# 1V2-BUCK.net
KiCad netlist of a schematic drawn in Altium Designer
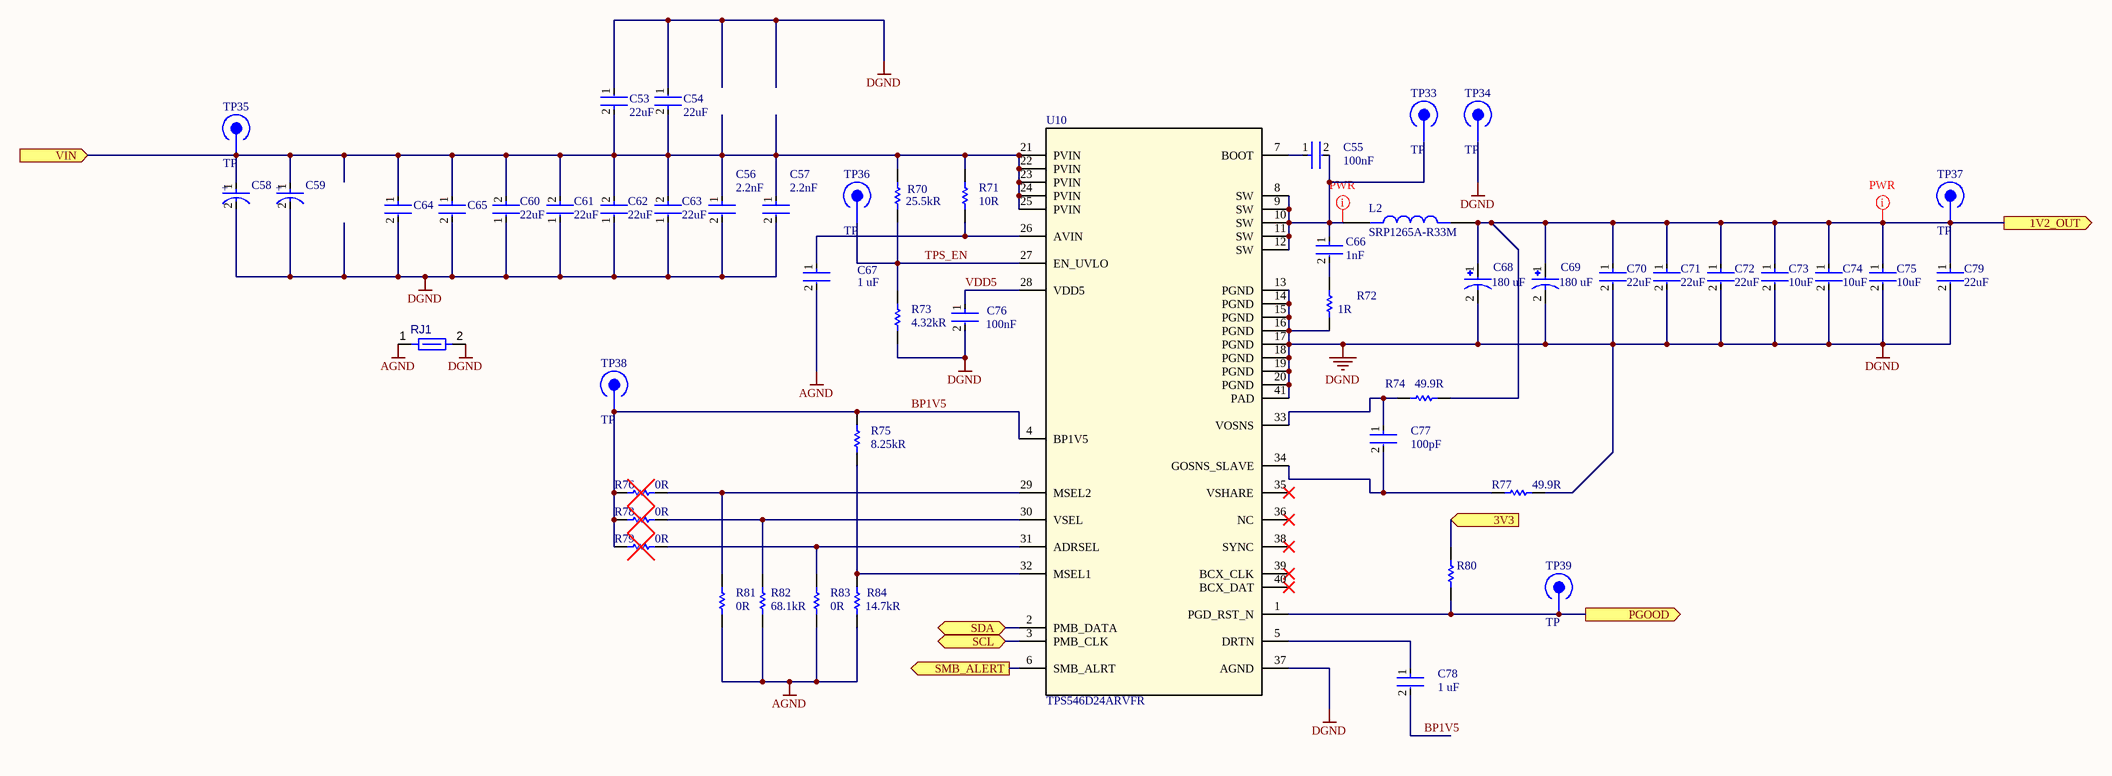
[diagram p0: 1V2-BUCK.SchDoc]

(export (version "E")
  (design (tool "Eeschema 10.0.6"))
  (components
    (comp (ref "C53")
      (value "GRM31CC81E226ME11L")
      (footprint "FP-GRM31C-0_3-e0_3_0_8-MFG")
      (description "Chip Multilayer Ceramic Capacitors for General Purpose, 1206, 22uF, X6S, 22%, 20%, 25V")
      (fields (field (name "CAPACITANCE") "22uF") (field (name "TOLERANCE") "20%"))
      (libsource (lib "Altium Content Vault") (part "f23184f103b6ebe33a8c269c53dcba6"))
    )
    (comp (ref "C54")
      (value "GRM31CC81E226ME11L")
      (footprint "FP-GRM31C-0_3-e0_3_0_8-MFG")
      (description "Chip Multilayer Ceramic Capacitors for General Purpose, 1206, 22uF, X6S, 22%, 20%, 25V")
      (fields (field (name "CAPACITANCE") "22uF") (field (name "TOLERANCE") "20%"))
      (libsource (lib "Altium Content Vault") (part "f23184f103b6ebe33a8c269c53dcba6"))
    )
    (comp (ref "C55")
      (value "100nF")
      (footprint "FP-CC0402-IPC_B")
      (fields (field (name "Comment") "CC0402KRX7R9BB104"))
      (libsource (lib "Digital Shovel") (part "11868f565c42a9108669ba33697ecf6"))
    )
    (comp (ref "C56")
      (value "2.2nF")
      (footprint "FP-CC0402-MFG")
      (fields (field (name "Comment") "CC0402KRX7R8BB222"))
      (libsource (lib "Digital Shovel") (part "11868f565c42a9108669ba33697ecf6"))
    )
    (comp (ref "C57")
      (value "2.2nF")
      (footprint "FP-CC0402-MFG")
      (fields (field (name "Comment") "CC0402KRX7R8BB222"))
      (libsource (lib "Digital Shovel") (part "11868f565c42a9108669ba33697ecf6"))
    )
    (comp (ref "C58")
      (value "593D107X9020E2TE3")
      (footprint "593D107X9020E2TE3-Footprint-1")
      (description "No Description Available")
      (libsource (lib "Digital Shovel") (part "593D107X9020E2TE3"))
    )
    (comp (ref "C59")
      (value "593D107X9020E2TE3")
      (footprint "593D107X9020E2TE3-Footprint-1")
      (description "No Description Available")
      (libsource (lib "Digital Shovel") (part "593D107X9020E2TE3"))
    )
    (comp (ref "C60")
      (value "GRM31CC81E226ME11L")
      (footprint "FP-GRM31C-0_3-e0_3_0_8-MFG")
      (description "Chip Multilayer Ceramic Capacitors for General Purpose, 1206, 22uF, X6S, 22%, 20%, 25V")
      (fields (field (name "CAPACITANCE") "22uF") (field (name "TOLERANCE") "20%"))
      (libsource (lib "Altium Content Vault") (part "f23184f103b6ebe33a8c269c53dcba6"))
    )
    (comp (ref "C61")
      (value "GRM31CC81E226ME11L")
      (footprint "FP-GRM31C-0_3-e0_3_0_8-MFG")
      (description "Chip Multilayer Ceramic Capacitors for General Purpose, 1206, 22uF, X6S, 22%, 20%, 25V")
      (fields (field (name "CAPACITANCE") "22uF") (field (name "TOLERANCE") "20%"))
      (libsource (lib "Altium Content Vault") (part "f23184f103b6ebe33a8c269c53dcba6"))
    )
    (comp (ref "C62")
      (value "GRM31CC81E226ME11L")
      (footprint "FP-GRM31C-0_3-e0_3_0_8-MFG")
      (description "Chip Multilayer Ceramic Capacitors for General Purpose, 1206, 22uF, X6S, 22%, 20%, 25V")
      (fields (field (name "CAPACITANCE") "22uF") (field (name "TOLERANCE") "20%"))
      (libsource (lib "Altium Content Vault") (part "f23184f103b6ebe33a8c269c53dcba6"))
    )
    (comp (ref "C63")
      (value "GRM31CC81E226ME11L")
      (footprint "FP-GRM31C-0_3-e0_3_0_8-MFG")
      (description "Chip Multilayer Ceramic Capacitors for General Purpose, 1206, 22uF, X6S, 22%, 20%, 25V")
      (fields (field (name "CAPACITANCE") "22uF") (field (name "TOLERANCE") "20%"))
      (libsource (lib "Altium Content Vault") (part "f23184f103b6ebe33a8c269c53dcba6"))
    )
    (comp (ref "C64")
      (value "C3216X5R1E476M160AC")
      (footprint "FP-C3216-160-0_2-MFG")
      (description "Multilayer Ceramic Capacitors 47uF ±20% 25V X5R SMD 1206")
      (fields (field (name "VOLTAGE") "25V") (field (name "TOLERANCE") "20%"))
      (libsource (lib "Altium Content Vault") (part "11868f565c42a9108669ba33697ecf6"))
    )
    (comp (ref "C65")
      (value "C3216X5R1E476M160AC")
      (footprint "FP-C3216-160-0_2-MFG")
      (description "Multilayer Ceramic Capacitors 47uF ±20% 25V X5R SMD 1206")
      (fields (field (name "VOLTAGE") "25V") (field (name "TOLERANCE") "20%"))
      (libsource (lib "Altium Content Vault") (part "11868f565c42a9108669ba33697ecf6"))
    )
    (comp (ref "C66")
      (value "1nF")
      (footprint "FP-CC0805-0_85-MFG")
      (fields (field (name "Comment") "CC0805KRX7R9BB102"))
      (libsource (lib "Digital Shovel") (part "11868f565c42a9108669ba33697ecf6"))
    )
    (comp (ref "C67")
      (value "1 uF")
      (footprint "FP-CC0402-MFG")
      (description "CAP CER 1UF 10V X5R 0402")
      (fields
        (field (name "OCTOPART") "https://octopart.com/cc0402krx5r6bb105-yageo-42244620")
        (field (name "MANUFACTURER PART NUMBER") "CC0402KRX5R6BB105")
      )
      (libsource (lib "Altium Content Vault") (part "11868f565c42a9108669ba33697ecf6"))
    )
    (comp (ref "C68")
      (value "180 uF")
      (footprint "EEF-SX0J181ER-Footprint-1")
      (description "Cap Aluminum Polymer 180uF 6.3VDC 20%( 7.3 X 4.3 X 1.9mm) SMD 0.009 Ohm 6300mA 2000h 105C T/R")
      (fields (field (name "MANUFACTURER") "Panasonic") (field (name "Comment") "EEF-SX0J181ER"))
      (libsource (lib "Digital Shovel") (part "EEF-SX0J181ER-Symbol-1"))
    )
    (comp (ref "C69")
      (value "180 uF")
      (footprint "EEF-SX0J181ER-Footprint-1")
      (description "Cap Aluminum Polymer 180uF 6.3VDC 20%( 7.3 X 4.3 X 1.9mm) SMD 0.009 Ohm 6300mA 2000h 105C T/R")
      (fields (field (name "MANUFACTURER") "Panasonic") (field (name "Comment") "EEF-SX0J181ER"))
      (libsource (lib "Digital Shovel") (part "EEF-SX0J181ER-Symbol-1"))
    )
    (comp (ref "C70")
      (value "22uF")
      (footprint "FP-GRM21B-0_2-e0_2_0_7-MFG")
      (fields (field (name "Comment") "GRM21BZ70J226ME44L"))
      (libsource (lib "Digital Shovel") (part "b4654b650e69147ec39a6b967a45e02"))
    )
    (comp (ref "C71")
      (value "22uF")
      (footprint "FP-GRM21B-0_2-e0_2_0_7-MFG")
      (fields (field (name "Comment") "GRM21BZ70J226ME44L"))
      (libsource (lib "Digital Shovel") (part "b4654b650e69147ec39a6b967a45e02"))
    )
    (comp (ref "C72")
      (value "22uF")
      (footprint "FP-GRM21B-0_2-e0_2_0_7-MFG")
      (fields (field (name "Comment") "GRM21BZ70J226ME44L"))
      (libsource (lib "Digital Shovel") (part "b4654b650e69147ec39a6b967a45e02"))
    )
    (comp (ref "C73")
      (value "10uF")
      (footprint "FP-GRM21B-0_15-MFG")
      (fields (field (name "Comment") "GRM21BR71A106KA73L"))
      (libsource (lib "Digital Shovel") (part "b4654b650e69147ec39a6b967a45e02"))
    )
    (comp (ref "C74")
      (value "10uF")
      (footprint "FP-GRM21B-0_15-MFG")
      (fields (field (name "Comment") "GRM21BR71A106KA73L"))
      (libsource (lib "Digital Shovel") (part "b4654b650e69147ec39a6b967a45e02"))
    )
    (comp (ref "C75")
      (value "10uF")
      (footprint "FP-GRM21B-0_15-MFG")
      (fields (field (name "Comment") "GRM21BR71A106KA73L"))
      (libsource (lib "Digital Shovel") (part "b4654b650e69147ec39a6b967a45e02"))
    )
    (comp (ref "C76")
      (value "100nF")
      (footprint "FP-CC0402-IPC_B")
      (fields (field (name "Comment") "CC0402KRX7R9BB104"))
      (libsource (lib "Digital Shovel") (part "11868f565c42a9108669ba33697ecf6"))
    )
    (comp (ref "C77")
      (value "100pF")
      (footprint "FP-CC0402-MFG")
      (fields (field (name "Comment") "CC0402KRX7R9BB101"))
      (libsource (lib "Digital Shovel") (part "11868f565c42a9108669ba33697ecf6"))
    )
    (comp (ref "C78")
      (value "1 uF")
      (footprint "FP-CC0402-MFG")
      (description "CAP CER 1UF 10V X5R 0402")
      (fields
        (field (name "OCTOPART") "https://octopart.com/cc0402krx5r6bb105-yageo-42244620")
        (field (name "MANUFACTURER PART NUMBER") "CC0402KRX5R6BB105")
      )
      (libsource (lib "Altium Content Vault") (part "11868f565c42a9108669ba33697ecf6"))
    )
    (comp (ref "C79")
      (value "22uF")
      (footprint "FP-GRM21B-0_2-e0_2_0_7-MFG")
      (fields (field (name "Comment") "GRM21BZ70J226ME44L"))
      (libsource (lib "Digital Shovel") (part "b4654b650e69147ec39a6b967a45e02"))
    )
    (comp (ref "L2")
      (value "SRP1265A-R33M")
      (footprint "SRP1265A-R33M")
      (description "General Purpose Inductor, 0.33uH, 20%, 1 Element, Carbonyl Powder-Core, SMD, 5349")
      (fields (field (name "TOLERANCE") "20%"))
      (libsource (lib "Digital Shovel") (part "SRP1265A-R33M"))
    )
    (comp (ref "R70")
      (value "25.5kR")
      (footprint "RESC1005X40X25LL10T10")
      (description "BOM UPDATE 25.5K (NEW) RESISTOR FROM 11.7K (OLD)\r\n\r\nNEW: RK73H1ETTP2552F")
      (fields (field (name "Comment") "RK73H1ETTP2552F"))
      (libsource (lib "Digital Shovel") (part "RES"))
    )
    (comp (ref "R71")
      (value "10R")
      (footprint "RESC1005X40X25LL10T10")
      (fields (field (name "Comment") "RK73H1ETTP10R0F"))
      (libsource (lib "Digital Shovel") (part "RES"))
    )
    (comp (ref "R72")
      (value "1R")
      (footprint "FP-RK73H2E-MFG")
      (fields (field (name "MANUFACTURER") "KOA Speer") (field (name "Comment") "RK73H2ETTD1R00F"))
      (libsource (lib "Digital Shovel") (part "1029c3af85768c4190bb7ad29bc67b5"))
    )
    (comp (ref "R73")
      (value "4.32kR")
      (footprint "RESC1005X40X25ML10T10")
      (description "BOM UPDATE 4.32K (NEW) RESISTOR FROM 37.4K (OLD)\r\n\r\nNEW: RK73H1ETTP4321F")
      (fields (field (name "MANUFACTURER") "KOA Speer") (field (name "PART NUMBER") "RK73H1ETTP3741F"))
      (libsource (lib "Altium Content Vault") (part "RES"))
    )
    (comp (ref "R74")
      (value "49.9R")
      (footprint "RESC1005X40X25LL10T10")
      (fields (field (name "Comment") "RK73H1ETTP49R9F"))
      (libsource (lib "Digital Shovel") (part "RES"))
    )
    (comp (ref "R75")
      (value "8.25kR")
      (footprint "RESC1005X40X25NL10T10")
      (fields (field (name "MANUFACTURER") "KOA Speer") (field (name "PART NUMBER") "RK73H1ETTP8251F"))
      (libsource (lib "Altium Content Vault") (part "RES"))
    )
    (comp (ref "R76")
      (value "0R")
      (footprint "FP-RK73Z1E-IPC_B")
      (description "Metal Glaze/thick Film, 0ohm, Surface Mount, 0402")
      (fields (field (name "Comment") "RK73Z1ETTP"))
      (libsource (lib "Digital Shovel") (part "1029c3af85768c4190bb7ad29bc67b5"))
    )
    (comp (ref "R77")
      (value "49.9R")
      (footprint "RESC1005X40X25LL10T10")
      (fields (field (name "Comment") "RK73H1ETTP49R9F"))
      (libsource (lib "Digital Shovel") (part "RES"))
    )
    (comp (ref "R78")
      (value "0R")
      (footprint "FP-RK73Z1E-IPC_B")
      (description "Metal Glaze/thick Film, 0ohm, Surface Mount, 0402")
      (fields (field (name "Comment") "RK73Z1ETTP"))
      (libsource (lib "Digital Shovel") (part "1029c3af85768c4190bb7ad29bc67b5"))
    )
    (comp (ref "R79")
      (value "0R")
      (footprint "FP-RK73Z1E-IPC_B")
      (description "Metal Glaze/thick Film, 0ohm, Surface Mount, 0402")
      (fields (field (name "Comment") "RK73Z1ETTP"))
      (libsource (lib "Digital Shovel") (part "1029c3af85768c4190bb7ad29bc67b5"))
    )
    (comp (ref "R80")
      (value "RK73H1ETTP1002F")
      (footprint "RESC1005X40X25LL10T10")
      (libsource (lib "Digital Shovel") (part "RES"))
    )
    (comp (ref "R81")
      (value "0R")
      (footprint "FP-RK73Z1E-IPC_B")
      (description "Metal Glaze/thick Film, 0ohm, Surface Mount, 0402")
      (fields (field (name "Comment") "RK73Z1ETTP"))
      (libsource (lib "Digital Shovel") (part "1029c3af85768c4190bb7ad29bc67b5"))
    )
    (comp (ref "R82")
      (value "68.1kR")
      (footprint "RESC1005X40X25LL10T10")
      (fields (field (name "Comment") "RK73H1ETTP6812F"))
      (libsource (lib "Digital Shovel") (part "RES"))
    )
    (comp (ref "R83")
      (value "0R")
      (footprint "FP-RK73Z1E-IPC_B")
      (description "Metal Glaze/thick Film, 0ohm, Surface Mount, 0402")
      (fields (field (name "Comment") "RK73Z1ETTP"))
      (libsource (lib "Digital Shovel") (part "1029c3af85768c4190bb7ad29bc67b5"))
    )
    (comp (ref "R84")
      (value "14.7kR")
      (footprint "RESC1005X40X25LL10T10")
      (fields (field (name "Comment") "RK73H1ETTP1472F"))
      (libsource (lib "Digital Shovel") (part "RES"))
    )
    (comp (ref "RJ1")
      (value "Net Tie 12x8mil")
      (footprint "SHORT06-FP")
      (libsource (lib "Digital Shovel") (part "CMP-00022-00002-2"))
    )
    (comp (ref "TP33")
      (value "TP")
      (footprint "TP-Footprint-1")
      (description "digital shovel test point")
      (libsource (lib "Digital Shovel") (part "TP-Symbol-1"))
    )
    (comp (ref "TP34")
      (value "TP")
      (footprint "TP-Footprint-1")
      (description "digital shovel test point")
      (libsource (lib "Digital Shovel") (part "TP-Symbol-1"))
    )
    (comp (ref "TP35")
      (value "TP")
      (footprint "TP-Footprint-1")
      (description "digital shovel test point")
      (libsource (lib "Digital Shovel") (part "TP-Symbol-1"))
    )
    (comp (ref "TP36")
      (value "TP")
      (footprint "TP-Footprint-1")
      (description "digital shovel test point")
      (libsource (lib "Digital Shovel") (part "TP-Symbol-1"))
    )
    (comp (ref "TP37")
      (value "TP")
      (footprint "TP-Footprint-1")
      (description "digital shovel test point")
      (libsource (lib "Digital Shovel") (part "TP-Symbol-1"))
    )
    (comp (ref "TP38")
      (value "TP")
      (footprint "TP-Footprint-1")
      (description "digital shovel test point")
      (libsource (lib "Digital Shovel") (part "TP-Symbol-1"))
    )
    (comp (ref "TP39")
      (value "TP")
      (footprint "TP-Footprint-1")
      (description "digital shovel test point")
      (libsource (lib "Digital Shovel") (part "TP-Symbol-1"))
    )
    (comp (ref "U10")
      (value "TPS546D24ARVFR")
      (footprint "TPS546D24ARVFR-Footprint-1")
      (description "Switching Regulator, Current-mode, 40A, 1500kHz Switching Freq-Max, PQCC40")
      (libsource (lib "Digital Shovel") (part "TPS546D24ARVFR-Symbol-1"))
    )
  )
  (nets
    (net (code "1") (name "/1V2_OUT") (class "Default")
      (node (ref "C68") (pin "1") (pinfunction "1_1") (pintype "passive"))
      (node (ref "C69") (pin "1") (pinfunction "1_1") (pintype "passive"))
      (node (ref "C70") (pin "1") (pinfunction "1_1") (pintype "passive"))
      (node (ref "C71") (pin "1") (pinfunction "1_1") (pintype "passive"))
      (node (ref "C72") (pin "1") (pinfunction "1_1") (pintype "passive"))
      (node (ref "C73") (pin "1") (pinfunction "1_1") (pintype "passive"))
      (node (ref "C74") (pin "1") (pinfunction "1_1") (pintype "passive"))
      (node (ref "C75") (pin "1") (pinfunction "1_1") (pintype "passive"))
      (node (ref "C79") (pin "1") (pinfunction "1_1") (pintype "passive"))
      (node (ref "L2") (pin "2") (pinfunction "2_2") (pintype "passive"))
      (node (ref "R74") (pin "2") (pinfunction "2_2") (pintype "passive"))
      (node (ref "TP37") (pin "1") (pintype "passive"))
    )
    (net (code "2") (name "/3V3") (class "Default")
      (node (ref "R80") (pin "2") (pinfunction "2_2") (pintype "passive"))
    )
    (net (code "3") (name "/BP1V5") (class "Default")
      (node (ref "C78") (pin "2") (pinfunction "2_2") (pintype "passive"))
      (node (ref "R75") (pin "1") (pinfunction "1_1") (pintype "passive"))
      (node (ref "R76") (pin "2") (pinfunction "2_2") (pintype "passive"))
      (node (ref "R78") (pin "2") (pinfunction "2_2") (pintype "passive"))
      (node (ref "R79") (pin "2") (pinfunction "2_2") (pintype "passive"))
      (node (ref "TP38") (pin "1") (pintype "passive"))
      (node (ref "U10") (pin "4") (pinfunction "BP1V5_4") (pintype "passive"))
    )
    (net (code "4") (name "/PGOOD") (class "Default")
      (node (ref "R80") (pin "1") (pinfunction "1_1") (pintype "passive"))
      (node (ref "TP39") (pin "1") (pintype "passive"))
      (node (ref "U10") (pin "1") (pinfunction "PGD_RST_N_1") (pintype "passive"))
    )
    (net (code "5") (name "/SCL") (class "Default")
      (node (ref "U10") (pin "3") (pinfunction "PMB_CLK_3") (pintype "passive"))
    )
    (net (code "6") (name "/SDA") (class "Default")
      (node (ref "U10") (pin "2") (pinfunction "PMB_DATA_2") (pintype "passive"))
    )
    (net (code "7") (name "/SMB_ALERT") (class "Default")
      (node (ref "U10") (pin "6") (pinfunction "SMB_ALRT_6") (pintype "passive"))
    )
    (net (code "8") (name "/TPS_EN") (class "Default")
      (node (ref "R70") (pin "1") (pinfunction "1_1") (pintype "passive"))
      (node (ref "R73") (pin "2") (pinfunction "2_2") (pintype "passive"))
      (node (ref "TP36") (pin "1") (pintype "passive"))
      (node (ref "U10") (pin "27") (pinfunction "EN_UVLO_27") (pintype "passive"))
    )
    (net (code "9") (name "/VDD5") (class "Default")
      (node (ref "C76") (pin "1") (pinfunction "1_1") (pintype "passive"))
      (node (ref "U10") (pin "28") (pinfunction "VDD5_28") (pintype "power_in"))
    )
    (net (code "10") (name "/VIN") (class "Default")
      (node (ref "C53") (pin "2") (pinfunction "2_2") (pintype "passive"))
      (node (ref "C54") (pin "2") (pinfunction "2_2") (pintype "passive"))
      (node (ref "C56") (pin "1") (pinfunction "1_1") (pintype "passive"))
      (node (ref "C57") (pin "1") (pinfunction "1_1") (pintype "passive"))
      (node (ref "C58") (pin "1") (pinfunction "A_1") (pintype "passive"))
      (node (ref "C59") (pin "1") (pinfunction "A_1") (pintype "passive"))
      (node (ref "C60") (pin "2") (pinfunction "2_2") (pintype "passive"))
      (node (ref "C61") (pin "2") (pinfunction "2_2") (pintype "passive"))
      (node (ref "C62") (pin "2") (pinfunction "2_2") (pintype "passive"))
      (node (ref "C63") (pin "2") (pinfunction "2_2") (pintype "passive"))
      (node (ref "C64") (pin "1") (pinfunction "1_1") (pintype "passive"))
      (node (ref "C65") (pin "1") (pinfunction "1_1") (pintype "passive"))
      (node (ref "R70") (pin "2") (pinfunction "2_2") (pintype "passive"))
      (node (ref "R71") (pin "2") (pinfunction "2_2") (pintype "passive"))
      (node (ref "TP35") (pin "1") (pintype "passive"))
      (node (ref "U10") (pin "21") (pinfunction "PVIN_21") (pintype "power_in"))
      (node (ref "U10") (pin "22") (pinfunction "PVIN_22") (pintype "power_in"))
      (node (ref "U10") (pin "23") (pinfunction "PVIN_23") (pintype "power_in"))
      (node (ref "U10") (pin "24") (pinfunction "PVIN_24") (pintype "power_in"))
      (node (ref "U10") (pin "25") (pinfunction "PVIN_25") (pintype "power_in"))
    )
    (net (code "11") (name "AGND") (class "Default")
      (node (ref "C67") (pin "2") (pinfunction "2_2") (pintype "passive"))
      (node (ref "R81") (pin "1") (pinfunction "1_1") (pintype "passive"))
      (node (ref "R82") (pin "1") (pinfunction "1_1") (pintype "passive"))
      (node (ref "R83") (pin "1") (pinfunction "1_1") (pintype "passive"))
      (node (ref "R84") (pin "1") (pinfunction "1_1") (pintype "passive"))
      (node (ref "RJ1") (pin "1") (pinfunction "1_1") (pintype "passive"))
    )
    (net (code "12") (name "DGND") (class "Default")
      (node (ref "C53") (pin "1") (pinfunction "1_1") (pintype "passive"))
      (node (ref "C54") (pin "1") (pinfunction "1_1") (pintype "passive"))
      (node (ref "C56") (pin "2") (pinfunction "2_2") (pintype "passive"))
      (node (ref "C57") (pin "2") (pinfunction "2_2") (pintype "passive"))
      (node (ref "C58") (pin "2") (pinfunction "C_2") (pintype "passive"))
      (node (ref "C59") (pin "2") (pinfunction "C_2") (pintype "passive"))
      (node (ref "C60") (pin "1") (pinfunction "1_1") (pintype "passive"))
      (node (ref "C61") (pin "1") (pinfunction "1_1") (pintype "passive"))
      (node (ref "C62") (pin "1") (pinfunction "1_1") (pintype "passive"))
      (node (ref "C63") (pin "1") (pinfunction "1_1") (pintype "passive"))
      (node (ref "C64") (pin "2") (pinfunction "2_2") (pintype "passive"))
      (node (ref "C65") (pin "2") (pinfunction "2_2") (pintype "passive"))
      (node (ref "C68") (pin "2") (pinfunction "2_2") (pintype "passive"))
      (node (ref "C69") (pin "2") (pinfunction "2_2") (pintype "passive"))
      (node (ref "C70") (pin "2") (pinfunction "2_2") (pintype "passive"))
      (node (ref "C71") (pin "2") (pinfunction "2_2") (pintype "passive"))
      (node (ref "C72") (pin "2") (pinfunction "2_2") (pintype "passive"))
      (node (ref "C73") (pin "2") (pinfunction "2_2") (pintype "passive"))
      (node (ref "C74") (pin "2") (pinfunction "2_2") (pintype "passive"))
      (node (ref "C75") (pin "2") (pinfunction "2_2") (pintype "passive"))
      (node (ref "C76") (pin "2") (pinfunction "2_2") (pintype "passive"))
      (node (ref "C79") (pin "2") (pinfunction "2_2") (pintype "passive"))
      (node (ref "R72") (pin "1") (pinfunction "1_1") (pintype "passive"))
      (node (ref "R73") (pin "1") (pinfunction "1_1") (pintype "passive"))
      (node (ref "R77") (pin "2") (pinfunction "2_2") (pintype "passive"))
      (node (ref "RJ1") (pin "2") (pinfunction "2_2") (pintype "passive"))
      (node (ref "TP34") (pin "1") (pintype "passive"))
      (node (ref "U10") (pin "13") (pinfunction "PGND_13") (pintype "power_in"))
      (node (ref "U10") (pin "14") (pinfunction "PGND_14") (pintype "power_in"))
      (node (ref "U10") (pin "15") (pinfunction "PGND_15") (pintype "power_in"))
      (node (ref "U10") (pin "16") (pinfunction "PGND_16") (pintype "power_in"))
      (node (ref "U10") (pin "17") (pinfunction "PGND_17") (pintype "power_in"))
      (node (ref "U10") (pin "18") (pinfunction "PGND_18") (pintype "power_in"))
      (node (ref "U10") (pin "19") (pinfunction "PGND_19") (pintype "power_in"))
      (node (ref "U10") (pin "20") (pinfunction "PGND_20") (pintype "power_in"))
      (node (ref "U10") (pin "37") (pinfunction "AGND_37") (pintype "power_in"))
      (node (ref "U10") (pin "41") (pinfunction "PAD_41") (pintype "power_in"))
    )
    (net (code "13") (name "Net-(C55-Pad2)") (class "Default")
      (node (ref "C55") (pin "2") (pinfunction "2_2") (pintype "passive"))
      (node (ref "C66") (pin "1") (pinfunction "1_1") (pintype "passive"))
      (node (ref "L2") (pin "1") (pinfunction "1_1") (pintype "passive"))
      (node (ref "TP33") (pin "1") (pintype "passive"))
      (node (ref "U10") (pin "10") (pinfunction "SW_10") (pintype "power_in"))
      (node (ref "U10") (pin "11") (pinfunction "SW_11") (pintype "power_in"))
      (node (ref "U10") (pin "12") (pinfunction "SW_12") (pintype "power_in"))
      (node (ref "U10") (pin "8") (pinfunction "SW_8") (pintype "power_in"))
      (node (ref "U10") (pin "9") (pinfunction "SW_9") (pintype "power_in"))
    )
    (net (code "14") (name "Net-(C66-Pad2)") (class "Default")
      (node (ref "C66") (pin "2") (pinfunction "2_2") (pintype "passive"))
      (node (ref "R72") (pin "2") (pinfunction "2_2") (pintype "passive"))
    )
    (net (code "15") (name "Net-(U10-ADRSEL)") (class "Default")
      (node (ref "R79") (pin "1") (pinfunction "1_1") (pintype "passive"))
      (node (ref "R83") (pin "2") (pinfunction "2_2") (pintype "passive"))
      (node (ref "U10") (pin "31") (pinfunction "ADRSEL_31") (pintype "passive"))
    )
    (net (code "16") (name "Net-(U10-AVIN)") (class "Default")
      (node (ref "C67") (pin "1") (pinfunction "1_1") (pintype "passive"))
      (node (ref "R71") (pin "1") (pinfunction "1_1") (pintype "passive"))
      (node (ref "U10") (pin "26") (pinfunction "AVIN_26") (pintype "power_in"))
    )
    (net (code "17") (name "Net-(U10-BOOT)") (class "Default")
      (node (ref "C55") (pin "1") (pinfunction "1_1") (pintype "passive"))
      (node (ref "U10") (pin "7") (pinfunction "BOOT_7") (pintype "power_in"))
    )
    (net (code "18") (name "Net-(U10-DRTN)") (class "Default")
      (node (ref "C78") (pin "1") (pinfunction "1_1") (pintype "passive"))
      (node (ref "U10") (pin "5") (pinfunction "DRTN_5") (pintype "power_in"))
    )
    (net (code "19") (name "Net-(U10-GOSNS_SLAVE)") (class "Default")
      (node (ref "C77") (pin "2") (pinfunction "2_2") (pintype "passive"))
      (node (ref "R77") (pin "1") (pinfunction "1_1") (pintype "passive"))
      (node (ref "U10") (pin "34") (pinfunction "GOSNS_SLAVE_34") (pintype "passive"))
    )
    (net (code "20") (name "Net-(U10-MSEL1)") (class "Default")
      (node (ref "R75") (pin "2") (pinfunction "2_2") (pintype "passive"))
      (node (ref "R84") (pin "2") (pinfunction "2_2") (pintype "passive"))
      (node (ref "U10") (pin "32") (pinfunction "MSEL1_32") (pintype "passive"))
    )
    (net (code "21") (name "Net-(U10-MSEL2)") (class "Default")
      (node (ref "R76") (pin "1") (pinfunction "1_1") (pintype "passive"))
      (node (ref "R81") (pin "2") (pinfunction "2_2") (pintype "passive"))
      (node (ref "U10") (pin "29") (pinfunction "MSEL2_29") (pintype "passive"))
    )
    (net (code "22") (name "Net-(U10-VOSNS)") (class "Default")
      (node (ref "C77") (pin "1") (pinfunction "1_1") (pintype "passive"))
      (node (ref "R74") (pin "1") (pinfunction "1_1") (pintype "passive"))
      (node (ref "U10") (pin "33") (pinfunction "VOSNS_33") (pintype "passive"))
    )
    (net (code "23") (name "Net-(U10-VSEL)") (class "Default")
      (node (ref "R78") (pin "1") (pinfunction "1_1") (pintype "passive"))
      (node (ref "R82") (pin "2") (pinfunction "2_2") (pintype "passive"))
      (node (ref "U10") (pin "30") (pinfunction "VSEL_30") (pintype "passive"))
    )
    (net (code "24") (name "unconnected-(U10-BCX_CLK-Pad39)") (class "Default")
      (node (ref "U10") (pin "39") (pinfunction "BCX_CLK_39") (pintype "passive+no_connect"))
    )
    (net (code "25") (name "unconnected-(U10-BCX_DAT-Pad40)") (class "Default")
      (node (ref "U10") (pin "40") (pinfunction "BCX_DAT_40") (pintype "passive+no_connect"))
    )
    (net (code "26") (name "unconnected-(U10-NC-Pad36)") (class "Default")
      (node (ref "U10") (pin "36") (pinfunction "NC_36") (pintype "passive+no_connect"))
    )
    (net (code "27") (name "unconnected-(U10-SYNC-Pad38)") (class "Default")
      (node (ref "U10") (pin "38") (pinfunction "SYNC_38") (pintype "passive+no_connect"))
    )
    (net (code "28") (name "unconnected-(U10-VSHARE-Pad35)") (class "Default")
      (node (ref "U10") (pin "35") (pinfunction "VSHARE_35") (pintype "passive+no_connect"))
    )
  )
)
